# top_level.net
KiCad netlist of a schematic drawn in Altium Designer
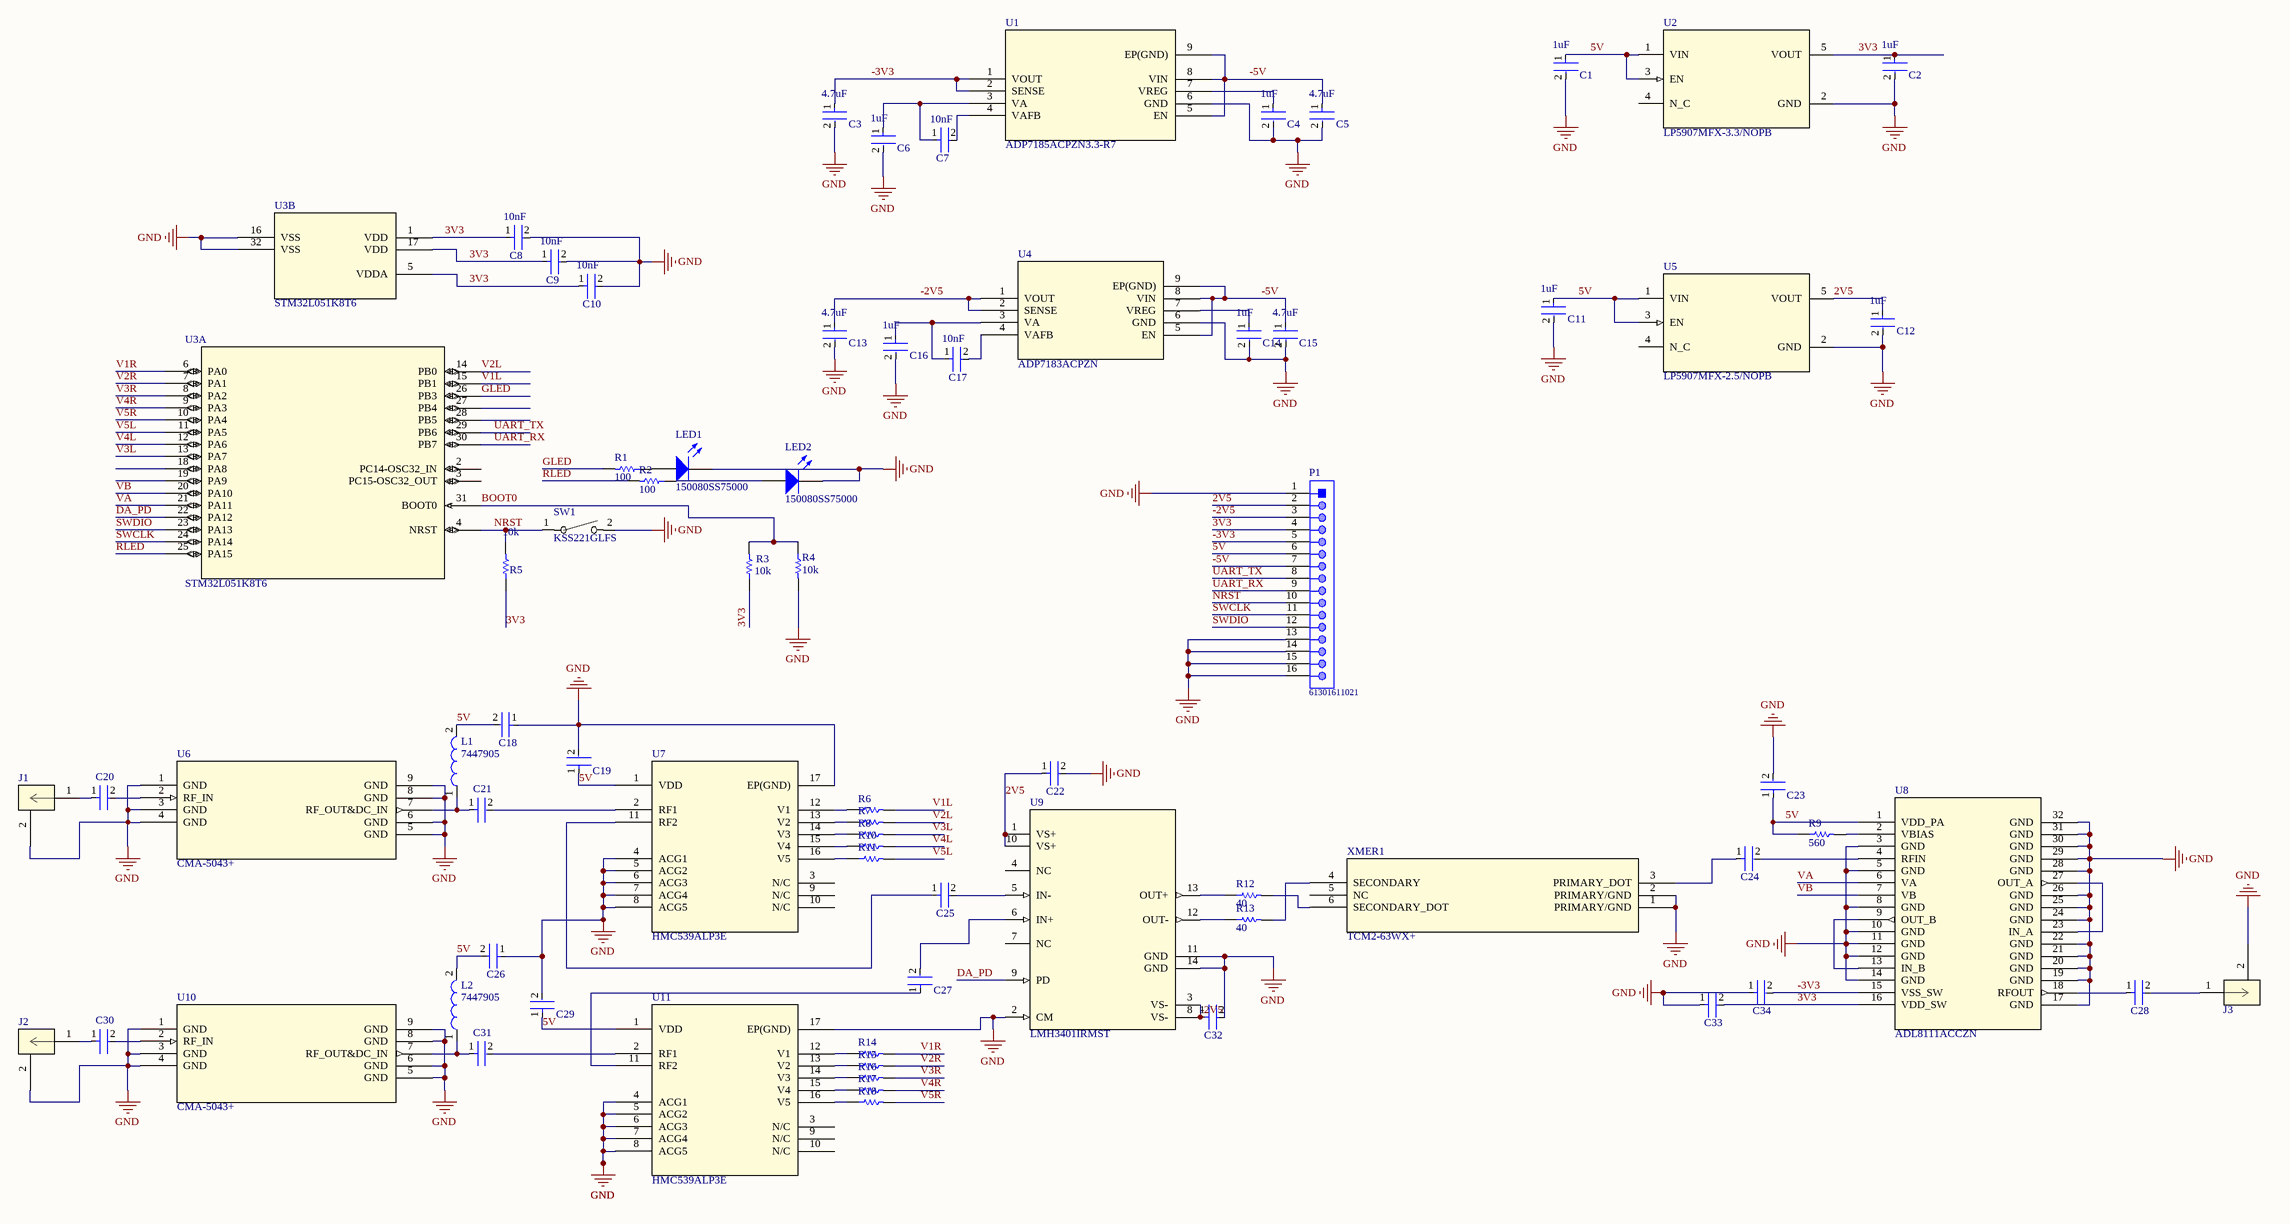
[diagram p0: top_level.SchDoc]

(export (version "E")
  (design (tool "Eeschema 10.0.6"))
  (components
    (comp (ref "C1")
      (value "1uF")
      (footprint "FP-C0402-BB-MFG")
      (description "CAP CER 0.1UF 10V X5R 0402")
      (fields (field (name "MANUFACTURER") "Kemet") (field (name "TOLERANCE") "0.1"))
      (libsource (lib "Altium Content Vault") (part "b4654b650e69147ec39a6b967a45e02"))
    )
    (comp (ref "C2")
      (value "1uF")
      (footprint "FP-C0402-BB-MFG")
      (description "CAP CER 0.1UF 10V X5R 0402")
      (fields (field (name "MANUFACTURER") "Kemet") (field (name "TOLERANCE") "0.1"))
      (libsource (lib "Altium Content Vault") (part "b4654b650e69147ec39a6b967a45e02"))
    )
    (comp (ref "C3")
      (value "4.7uF")
      (footprint "FP-C0402-BB-MFG")
      (description "CAP CER 0.1UF 10V X5R 0402")
      (fields (field (name "MANUFACTURER") "Kemet") (field (name "TOLERANCE") "0.1"))
      (libsource (lib "Altium Content Vault") (part "b4654b650e69147ec39a6b967a45e02"))
    )
    (comp (ref "C4")
      (value "1uF")
      (footprint "FP-C0402-BB-MFG")
      (description "CAP CER 0.1UF 10V X5R 0402")
      (fields (field (name "MANUFACTURER") "Kemet") (field (name "TOLERANCE") "0.1"))
      (libsource (lib "Altium Content Vault") (part "b4654b650e69147ec39a6b967a45e02"))
    )
    (comp (ref "C5")
      (value "4.7uF")
      (footprint "FP-C0402-BB-MFG")
      (description "CAP CER 0.1UF 10V X5R 0402")
      (fields (field (name "MANUFACTURER") "Kemet") (field (name "TOLERANCE") "0.1"))
      (libsource (lib "Altium Content Vault") (part "b4654b650e69147ec39a6b967a45e02"))
    )
    (comp (ref "C6")
      (value "1uF")
      (footprint "FP-C0402-BB-MFG")
      (description "CAP CER 0.1UF 10V X5R 0402")
      (fields (field (name "MANUFACTURER") "Kemet") (field (name "TOLERANCE") "0.1"))
      (libsource (lib "Altium Content Vault") (part "b4654b650e69147ec39a6b967a45e02"))
    )
    (comp (ref "C7")
      (value "10nF")
      (footprint "FP-C0402-BB-MFG")
      (description "CAP CER 0.1UF 10V X5R 0402")
      (fields (field (name "MANUFACTURER") "Kemet") (field (name "TOLERANCE") "0.1"))
      (libsource (lib "Altium Content Vault") (part "b4654b650e69147ec39a6b967a45e02"))
    )
    (comp (ref "C8")
      (value "10nF")
      (footprint "FP-C0402-BB-MFG")
      (description "CAP CER 0.1UF 10V X5R 0402")
      (fields (field (name "MANUFACTURER") "Kemet") (field (name "TOLERANCE") "0.1"))
      (libsource (lib "Altium Content Vault") (part "b4654b650e69147ec39a6b967a45e02"))
    )
    (comp (ref "C9")
      (value "10nF")
      (footprint "FP-C0402-BB-MFG")
      (description "CAP CER 0.1UF 10V X5R 0402")
      (fields (field (name "MANUFACTURER") "Kemet") (field (name "TOLERANCE") "0.1"))
      (libsource (lib "Altium Content Vault") (part "b4654b650e69147ec39a6b967a45e02"))
    )
    (comp (ref "C10")
      (value "10nF")
      (footprint "FP-C0402-BB-MFG")
      (description "CAP CER 0.1UF 10V X5R 0402")
      (fields (field (name "MANUFACTURER") "Kemet") (field (name "TOLERANCE") "0.1"))
      (libsource (lib "Altium Content Vault") (part "b4654b650e69147ec39a6b967a45e02"))
    )
    (comp (ref "C11")
      (value "1uF")
      (footprint "FP-C0402-BB-MFG")
      (description "CAP CER 0.1UF 10V X5R 0402")
      (fields (field (name "MANUFACTURER") "Kemet") (field (name "TOLERANCE") "0.1"))
      (libsource (lib "Altium Content Vault") (part "b4654b650e69147ec39a6b967a45e02"))
    )
    (comp (ref "C12")
      (value "1uF")
      (footprint "FP-C0402-BB-MFG")
      (description "CAP CER 0.1UF 10V X5R 0402")
      (fields (field (name "MANUFACTURER") "Kemet") (field (name "TOLERANCE") "0.1"))
      (libsource (lib "Altium Content Vault") (part "b4654b650e69147ec39a6b967a45e02"))
    )
    (comp (ref "C13")
      (value "4.7uF")
      (footprint "FP-C0402-BB-MFG")
      (description "CAP CER 0.1UF 10V X5R 0402")
      (fields (field (name "MANUFACTURER") "Kemet") (field (name "TOLERANCE") "0.1"))
      (libsource (lib "Altium Content Vault") (part "b4654b650e69147ec39a6b967a45e02"))
    )
    (comp (ref "C14")
      (value "1uF")
      (footprint "FP-C0402-BB-MFG")
      (description "CAP CER 0.1UF 10V X5R 0402")
      (fields (field (name "MANUFACTURER") "Kemet") (field (name "TOLERANCE") "0.1"))
      (libsource (lib "Altium Content Vault") (part "b4654b650e69147ec39a6b967a45e02"))
    )
    (comp (ref "C15")
      (value "4.7uF")
      (footprint "FP-C0402-BB-MFG")
      (description "CAP CER 0.1UF 10V X5R 0402")
      (fields (field (name "MANUFACTURER") "Kemet") (field (name "TOLERANCE") "0.1"))
      (libsource (lib "Altium Content Vault") (part "b4654b650e69147ec39a6b967a45e02"))
    )
    (comp (ref "C16")
      (value "1uF")
      (footprint "FP-C0402-BB-MFG")
      (description "CAP CER 0.1UF 10V X5R 0402")
      (fields (field (name "MANUFACTURER") "Kemet") (field (name "TOLERANCE") "0.1"))
      (libsource (lib "Altium Content Vault") (part "b4654b650e69147ec39a6b967a45e02"))
    )
    (comp (ref "C17")
      (value "10nF")
      (footprint "FP-C0402-BB-MFG")
      (description "CAP CER 0.1UF 10V X5R 0402")
      (fields (field (name "MANUFACTURER") "Kemet") (field (name "TOLERANCE") "0.1"))
      (libsource (lib "Altium Content Vault") (part "b4654b650e69147ec39a6b967a45e02"))
    )
    (comp (ref "C18")
      (value "C0402C104K8PACTU")
      (footprint "FP-C0402-BB-MFG")
      (description "CAP CER 0.1UF 10V X5R 0402")
      (fields (field (name "MANUFACTURER") "Kemet") (field (name "TOLERANCE") "0.1"))
      (libsource (lib "Altium Content Vault") (part "b4654b650e69147ec39a6b967a45e02"))
    )
    (comp (ref "C19")
      (value "C0402C104K8PACTU")
      (footprint "FP-C0402-BB-MFG")
      (description "CAP CER 0.1UF 10V X5R 0402")
      (fields (field (name "MANUFACTURER") "Kemet") (field (name "TOLERANCE") "0.1"))
      (libsource (lib "Altium Content Vault") (part "b4654b650e69147ec39a6b967a45e02"))
    )
    (comp (ref "C20")
      (value "C0402C104K8PACTU")
      (footprint "FP-C0402-BB-MFG")
      (description "CAP CER 0.1UF 10V X5R 0402")
      (fields (field (name "MANUFACTURER") "Kemet") (field (name "TOLERANCE") "0.1"))
      (libsource (lib "Altium Content Vault") (part "b4654b650e69147ec39a6b967a45e02"))
    )
    (comp (ref "C21")
      (value "C0402C104K8PACTU")
      (footprint "FP-C0402-BB-MFG")
      (description "CAP CER 0.1UF 10V X5R 0402")
      (fields (field (name "MANUFACTURER") "Kemet") (field (name "TOLERANCE") "0.1"))
      (libsource (lib "Altium Content Vault") (part "b4654b650e69147ec39a6b967a45e02"))
    )
    (comp (ref "C22")
      (value "C0402C104K8PACTU")
      (footprint "FP-C0402-BB-MFG")
      (description "CAP CER 0.1UF 10V X5R 0402")
      (fields (field (name "MANUFACTURER") "Kemet") (field (name "TOLERANCE") "0.1"))
      (libsource (lib "Altium Content Vault") (part "b4654b650e69147ec39a6b967a45e02"))
    )
    (comp (ref "C23")
      (value "C0402C104K8PACTU")
      (footprint "FP-C0402-BB-MFG")
      (description "CAP CER 0.1UF 10V X5R 0402")
      (fields (field (name "MANUFACTURER") "Kemet") (field (name "TOLERANCE") "0.1"))
      (libsource (lib "Altium Content Vault") (part "b4654b650e69147ec39a6b967a45e02"))
    )
    (comp (ref "C24")
      (value "C0402C104K8PACTU")
      (footprint "FP-C0402-BB-MFG")
      (description "CAP CER 0.1UF 10V X5R 0402")
      (fields (field (name "MANUFACTURER") "Kemet") (field (name "TOLERANCE") "0.1"))
      (libsource (lib "Altium Content Vault") (part "b4654b650e69147ec39a6b967a45e02"))
    )
    (comp (ref "C25")
      (value "C0402C104K8PACTU")
      (footprint "FP-C0402-BB-MFG")
      (description "CAP CER 0.1UF 10V X5R 0402")
      (fields (field (name "MANUFACTURER") "Kemet") (field (name "TOLERANCE") "0.1"))
      (libsource (lib "Altium Content Vault") (part "b4654b650e69147ec39a6b967a45e02"))
    )
    (comp (ref "C26")
      (value "C0402C104K8PACTU")
      (footprint "FP-C0402-BB-MFG")
      (description "CAP CER 0.1UF 10V X5R 0402")
      (fields (field (name "MANUFACTURER") "Kemet") (field (name "TOLERANCE") "0.1"))
      (libsource (lib "Altium Content Vault") (part "b4654b650e69147ec39a6b967a45e02"))
    )
    (comp (ref "C27")
      (value "C0402C104K8PACTU")
      (footprint "FP-C0402-BB-MFG")
      (description "CAP CER 0.1UF 10V X5R 0402")
      (fields (field (name "MANUFACTURER") "Kemet") (field (name "TOLERANCE") "0.1"))
      (libsource (lib "Altium Content Vault") (part "b4654b650e69147ec39a6b967a45e02"))
    )
    (comp (ref "C28")
      (value "C0402C104K8PACTU")
      (footprint "FP-C0402-BB-MFG")
      (description "CAP CER 0.1UF 10V X5R 0402")
      (fields (field (name "MANUFACTURER") "Kemet") (field (name "TOLERANCE") "0.1"))
      (libsource (lib "Altium Content Vault") (part "b4654b650e69147ec39a6b967a45e02"))
    )
    (comp (ref "C29")
      (value "C0402C104K8PACTU")
      (footprint "FP-C0402-BB-MFG")
      (description "CAP CER 0.1UF 10V X5R 0402")
      (fields (field (name "MANUFACTURER") "Kemet") (field (name "TOLERANCE") "0.1"))
      (libsource (lib "Altium Content Vault") (part "b4654b650e69147ec39a6b967a45e02"))
    )
    (comp (ref "C30")
      (value "C0402C104K8PACTU")
      (footprint "FP-C0402-BB-MFG")
      (description "CAP CER 0.1UF 10V X5R 0402")
      (fields (field (name "MANUFACTURER") "Kemet") (field (name "TOLERANCE") "0.1"))
      (libsource (lib "Altium Content Vault") (part "b4654b650e69147ec39a6b967a45e02"))
    )
    (comp (ref "C31")
      (value "C0402C104K8PACTU")
      (footprint "FP-C0402-BB-MFG")
      (description "CAP CER 0.1UF 10V X5R 0402")
      (fields (field (name "MANUFACTURER") "Kemet") (field (name "TOLERANCE") "0.1"))
      (libsource (lib "Altium Content Vault") (part "b4654b650e69147ec39a6b967a45e02"))
    )
    (comp (ref "C32")
      (value "C0402C104K8PACTU")
      (footprint "FP-C0402-BB-MFG")
      (description "CAP CER 0.1UF 10V X5R 0402")
      (fields (field (name "MANUFACTURER") "Kemet") (field (name "TOLERANCE") "0.1"))
      (libsource (lib "Altium Content Vault") (part "b4654b650e69147ec39a6b967a45e02"))
    )
    (comp (ref "C33")
      (value "C0402C104K8PACTU")
      (footprint "FP-C0402-BB-MFG")
      (description "CAP CER 0.1UF 10V X5R 0402")
      (fields (field (name "MANUFACTURER") "Kemet") (field (name "TOLERANCE") "0.1"))
      (libsource (lib "Altium Content Vault") (part "b4654b650e69147ec39a6b967a45e02"))
    )
    (comp (ref "C34")
      (value "C0402C104K8PACTU")
      (footprint "FP-C0402-BB-MFG")
      (description "CAP CER 0.1UF 10V X5R 0402")
      (fields (field (name "MANUFACTURER") "Kemet") (field (name "TOLERANCE") "0.1"))
      (libsource (lib "Altium Content Vault") (part "b4654b650e69147ec39a6b967a45e02"))
    )
    (comp (ref "J1")
      (value "142-0711-821")
      (footprint "CONN_142-0711-821_CIN")
      (description "No Description Available")
      (fields (field (name "COPYRIGHT") "Copyright (C) 2022 Ultra Librarian. All rights reserved."))
      (libsource (lib "") (part "142-0711-821_1"))
    )
    (comp (ref "J2")
      (value "142-0711-821")
      (footprint "CONN_142-0711-821_CIN")
      (description "No Description Available")
      (fields (field (name "COPYRIGHT") "Copyright (C) 2022 Ultra Librarian. All rights reserved."))
      (libsource (lib "") (part "142-0711-821_1"))
    )
    (comp (ref "J3")
      (value "142-0711-821")
      (footprint "CONN_142-0711-821_CIN")
      (description "No Description Available")
      (fields (field (name "COPYRIGHT") "Copyright (C) 2022 Ultra Librarian. All rights reserved."))
      (libsource (lib "142-0711-821") (part "142-0711-821"))
    )
    (comp (ref "L1")
      (value "7447905")
      (footprint "SMD-0805")
      (description "SMD-Multilayer Inductor WE-MI, L = 1.00 µH")
      (libsource (lib "Altium Content Vault") (part "PAS-IND-INDUCTOR-2"))
    )
    (comp (ref "L2")
      (value "7447905")
      (footprint "SMD-0805")
      (description "SMD-Multilayer Inductor WE-MI, L = 1.00 µH")
      (libsource (lib "Altium Content Vault") (part "PAS-IND-INDUCTOR-2"))
    )
    (comp (ref "LED1")
      (value "150080SS75000")
      (footprint "0805_A")
      (description "SMD mono-color Chip LED, WL-SMCW, Super Red")
      (fields (field (name "MANUFACTURER") "Wuerth Elektronik"))
      (libsource (lib "Altium Content Vault") (part "WE-LED_K1A2-2"))
    )
    (comp (ref "LED2")
      (value "150080SS75000")
      (footprint "0805_A")
      (description "SMD mono-color Chip LED, WL-SMCW, Super Red")
      (fields (field (name "MANUFACTURER") "Wuerth Elektronik"))
      (libsource (lib "Altium Content Vault") (part "WE-LED_K1A2-2"))
    )
    (comp (ref "P1")
      (value "61301611021")
      (footprint "61301611021")
      (description "THT Angled Pin Header WR-PHD, Pitch 2.54 mm, Single Row, 16 pins")
      (fields (field (name "MANUFACTURER") "Wurth Elektronik") (field (name "PUBLISHER") "WurthElektronik"))
      (libsource (lib "Altium Content Vault") (part "WE-CN-1P-M-R16"))
    )
    (comp (ref "R1")
      (value "100")
      (footprint "RESC1005X40X25NL05T10")
      (fields (field (name "MANUFACTURER") "Yageo / Phycomp") (field (name "PART NUMBER") "RC0402JR-070RL"))
      (libsource (lib "Altium Content Vault") (part "RES"))
    )
    (comp (ref "R2")
      (value "100")
      (footprint "RESC1005X40X25NL05T10")
      (fields (field (name "MANUFACTURER") "Yageo / Phycomp") (field (name "PART NUMBER") "RC0402JR-070RL"))
      (libsource (lib "Altium Content Vault") (part "RES"))
    )
    (comp (ref "R3")
      (value "10k")
      (footprint "RESC1005X40X25NL05T10")
      (fields (field (name "MANUFACTURER") "Yageo / Phycomp") (field (name "PART NUMBER") "RC0402JR-070RL"))
      (libsource (lib "Altium Content Vault") (part "RES"))
    )
    (comp (ref "R4")
      (value "10k")
      (footprint "RESC1005X40X25NL05T10")
      (fields (field (name "MANUFACTURER") "Yageo / Phycomp") (field (name "PART NUMBER") "RC0402JR-070RL"))
      (libsource (lib "Altium Content Vault") (part "RES"))
    )
    (comp (ref "R5")
      (value "10k")
      (footprint "RESC1005X40X25NL05T10")
      (fields (field (name "MANUFACTURER") "Yageo / Phycomp") (field (name "PART NUMBER") "RC0402JR-070RL"))
      (libsource (lib "Altium Content Vault") (part "RES"))
    )
    (comp (ref "R6")
      (value "RC0402JR-070RL")
      (footprint "RESC1005X40X25NL05T10")
      (fields (field (name "MANUFACTURER") "Yageo / Phycomp"))
      (libsource (lib "Altium Content Vault") (part "RES"))
    )
    (comp (ref "R7")
      (value "RC0402JR-070RL")
      (footprint "RESC1005X40X25NL05T10")
      (fields (field (name "MANUFACTURER") "Yageo / Phycomp"))
      (libsource (lib "Altium Content Vault") (part "RES"))
    )
    (comp (ref "R8")
      (value "RC0402JR-070RL")
      (footprint "RESC1005X40X25NL05T10")
      (fields (field (name "MANUFACTURER") "Yageo / Phycomp"))
      (libsource (lib "Altium Content Vault") (part "RES"))
    )
    (comp (ref "R9")
      (value "560")
      (footprint "RESC1005X40X25NL05T10")
      (fields (field (name "MANUFACTURER") "Yageo / Phycomp") (field (name "PART NUMBER") "RC0402JR-070RL"))
      (libsource (lib "Altium Content Vault") (part "RES"))
    )
    (comp (ref "R10")
      (value "RC0402JR-070RL")
      (footprint "RESC1005X40X25NL05T10")
      (fields (field (name "MANUFACTURER") "Yageo / Phycomp"))
      (libsource (lib "Altium Content Vault") (part "RES"))
    )
    (comp (ref "R11")
      (value "RC0402JR-070RL")
      (footprint "RESC1005X40X25NL05T10")
      (fields (field (name "MANUFACTURER") "Yageo / Phycomp"))
      (libsource (lib "Altium Content Vault") (part "RES"))
    )
    (comp (ref "R12")
      (value "40")
      (footprint "RESC1005X40X25NL05T10")
      (fields (field (name "MANUFACTURER") "Yageo / Phycomp") (field (name "PART NUMBER") "RC0402JR-070RL"))
      (libsource (lib "Altium Content Vault") (part "RES"))
    )
    (comp (ref "R13")
      (value "40")
      (footprint "RESC1005X40X25NL05T10")
      (fields (field (name "MANUFACTURER") "Yageo / Phycomp") (field (name "PART NUMBER") "RC0402JR-070RL"))
      (libsource (lib "Altium Content Vault") (part "RES"))
    )
    (comp (ref "R14")
      (value "RC0402JR-070RL")
      (footprint "RESC1005X40X25NL05T10")
      (fields (field (name "MANUFACTURER") "Yageo / Phycomp"))
      (libsource (lib "Altium Content Vault") (part "RES"))
    )
    (comp (ref "R15")
      (value "RC0402JR-070RL")
      (footprint "RESC1005X40X25NL05T10")
      (fields (field (name "MANUFACTURER") "Yageo / Phycomp"))
      (libsource (lib "Altium Content Vault") (part "RES"))
    )
    (comp (ref "R16")
      (value "RC0402JR-070RL")
      (footprint "RESC1005X40X25NL05T10")
      (fields (field (name "MANUFACTURER") "Yageo / Phycomp"))
      (libsource (lib "Altium Content Vault") (part "RES"))
    )
    (comp (ref "R17")
      (value "RC0402JR-070RL")
      (footprint "RESC1005X40X25NL05T10")
      (fields (field (name "MANUFACTURER") "Yageo / Phycomp"))
      (libsource (lib "Altium Content Vault") (part "RES"))
    )
    (comp (ref "R18")
      (value "RC0402JR-070RL")
      (footprint "RESC1005X40X25NL05T10")
      (fields (field (name "MANUFACTURER") "Yageo / Phycomp"))
      (libsource (lib "Altium Content Vault") (part "RES"))
    )
    (comp (ref "SW1")
      (value "KSS221GLFS")
      (footprint "SW_KSS221GLFS_CNK")
      (description "No Description Available")
      (fields (field (name "COPYRIGHT") "Copyright (C) 2022 Ultra Librarian. All rights reserved."))
      (libsource (lib "KSS221GLFS") (part "KSS221GLFS"))
    )
    (comp (ref "U1")
      (value "ADP7185ACPZN3.3-R7")
      (footprint "CP_8_27_ADI")
      (description "No Description Available")
      (fields (field (name "COPYRIGHT") "Copyright (C) 2022 Ultra Librarian. All rights reserved."))
      (libsource (lib "ADP7185ACPZN3P3-R7") (part "ADP7185ACPZN3.3-R7"))
    )
    (comp (ref "U2")
      (value "LP5907MFX-3.3/NOPB")
      (footprint "DBV0005A_L")
      (description "No Description Available")
      (fields (field (name "COPYRIGHT") "Copyright (C) 2022 Ultra Librarian. All rights reserved."))
      (libsource (lib "LP5907MFX-3P3&slash_NOPB") (part "LP5907MFX-3.3/NOPB"))
    )
    (comp (ref "U3")
      (value "STM32L051K8T6")
      (footprint "LQFP32_7X7X1P4")
      (description "No Description Available")
      (fields (field (name "COPYRIGHT") "Copyright (C) 2022 Ultra Librarian. All rights reserved."))
      (libsource (lib "STM32L051K8T6") (part "STM32L051K8T6"))
    )
    (comp (ref "U4")
      (value "ADP7183ACPZN")
      (footprint "CP-8-27_ADI")
      (description "No Description Available")
      (fields (field (name "COPYRIGHT") "Copyright (C) 2022 Ultra Librarian. All rights reserved."))
      (libsource (lib "ADP7183ACPZN") (part "ADP7183ACPZN"))
    )
    (comp (ref "U5")
      (value "LP5907MFX-2.5/NOPB")
      (footprint "DBV0005A_L")
      (description "No Description Available")
      (fields (field (name "COPYRIGHT") "Copyright (C) 2022 Ultra Librarian. All rights reserved."))
      (libsource (lib "LP5907MFX-2P5&slash_NOPB") (part "LP5907MFX-2.5/NOPB"))
    )
    (comp (ref "U6")
      (value "CMA-5043+")
      (footprint "DL1721_MNC")
      (description "No Description Available")
      (fields (field (name "COPYRIGHT") "Copyright (C) 2022 Ultra Librarian. All rights reserved."))
      (libsource (lib "CMA-5043&plus_") (part "CMA-5043+"))
    )
    (comp (ref "U7")
      (value "HMC539ALP3E")
      (footprint "HCP_16_1_ADI")
      (description "No Description Available")
      (fields (field (name "COPYRIGHT") "Copyright (C) 2022 Ultra Librarian. All rights reserved."))
      (libsource (lib "HMC539ALP3E") (part "HMC539ALP3E"))
    )
    (comp (ref "U8")
      (value "ADL8111ACCZN")
      (footprint "IC28_ADL8111ACCZN_ADI")
      (description "No Description Available")
      (fields (field (name "COPYRIGHT") "Copyright (C) 2022 Ultra Librarian. All rights reserved."))
      (libsource (lib "ADL8111ACCZN") (part "ADL8111ACCZN"))
    )
    (comp (ref "U9")
      (value "LMH3401IRMST")
      (footprint "RMS0014A")
      (description "No Description Available")
      (fields (field (name "COPYRIGHT") "Copyright (C) 2022 Ultra Librarian. All rights reserved."))
      (libsource (lib "LMH3401IRMST") (part "LMH3401IRMST"))
    )
    (comp (ref "U10")
      (value "CMA-5043+")
      (footprint "DL1721_MNC")
      (description "No Description Available")
      (fields (field (name "COPYRIGHT") "Copyright (C) 2022 Ultra Librarian. All rights reserved."))
      (libsource (lib "CMA-5043&plus_") (part "CMA-5043+"))
    )
    (comp (ref "U11")
      (value "HMC539ALP3E")
      (footprint "HCP_16_1_ADI")
      (description "No Description Available")
      (fields (field (name "COPYRIGHT") "Copyright (C) 2022 Ultra Librarian. All rights reserved."))
      (libsource (lib "HMC539ALP3E") (part "HMC539ALP3E"))
    )
    (comp (ref "XMER1")
      (value "TCM2-63WX+")
      (footprint "DB1627_MNC")
      (description "No Description Available")
      (fields (field (name "COPYRIGHT") "Copyright (C) 2022 Ultra Librarian. All rights reserved."))
      (libsource (lib "TCM2-63WX&plus_") (part "TCM2-63WX+"))
    )
  )
  (nets
    (net (code "1") (name "/-2V5") (class "Default")
      (node (ref "C13") (pin "1") (pinfunction "1_1") (pintype "passive"))
      (node (ref "C32") (pin "1") (pinfunction "1_1") (pintype "passive"))
      (node (ref "P1") (pin "3") (pinfunction "3_3") (pintype "passive"))
      (node (ref "U4") (pin "1") (pinfunction "VOUT_1") (pintype "passive"))
      (node (ref "U4") (pin "2") (pinfunction "SENSE_2") (pintype "passive"))
      (node (ref "U9") (pin "3") (pinfunction "VS-_3") (pintype "power_in"))
      (node (ref "U9") (pin "8") (pinfunction "VS-_8") (pintype "power_in"))
    )
    (net (code "2") (name "/-3V3") (class "Default")
      (node (ref "C3") (pin "1") (pinfunction "1_1") (pintype "passive"))
      (node (ref "C34") (pin "2") (pinfunction "2_2") (pintype "passive"))
      (node (ref "P1") (pin "5") (pinfunction "5_5") (pintype "passive"))
      (node (ref "U1") (pin "1") (pinfunction "VOUT_1") (pintype "passive"))
      (node (ref "U1") (pin "2") (pinfunction "SENSE_2") (pintype "passive"))
      (node (ref "U8") (pin "15") (pinfunction "VSS_SW_15") (pintype "passive"))
    )
    (net (code "3") (name "/-5V") (class "Default")
      (node (ref "C15") (pin "1") (pinfunction "1_1") (pintype "passive"))
      (node (ref "C5") (pin "1") (pinfunction "1_1") (pintype "passive"))
      (node (ref "P1") (pin "7") (pinfunction "7_7") (pintype "passive"))
      (node (ref "U1") (pin "5") (pinfunction "EN_5") (pintype "passive"))
      (node (ref "U1") (pin "8") (pinfunction "VIN_8") (pintype "passive"))
      (node (ref "U1") (pin "9") (pinfunction "EP(GND)_9") (pintype "passive"))
      (node (ref "U4") (pin "5") (pinfunction "EN_5") (pintype "passive"))
      (node (ref "U4") (pin "8") (pinfunction "VIN_8") (pintype "passive"))
      (node (ref "U4") (pin "9") (pinfunction "EP(GND)_9") (pintype "passive"))
    )
    (net (code "4") (name "/2V5") (class "Default")
      (node (ref "C12") (pin "1") (pinfunction "1_1") (pintype "passive"))
      (node (ref "C22") (pin "1") (pinfunction "1_1") (pintype "passive"))
      (node (ref "P1") (pin "2") (pinfunction "2_2") (pintype "passive"))
      (node (ref "U5") (pin "5") (pinfunction "VOUT_5") (pintype "power_in"))
      (node (ref "U9") (pin "1") (pinfunction "VS+_1") (pintype "power_in"))
      (node (ref "U9") (pin "10") (pinfunction "VS+_10") (pintype "power_in"))
    )
    (net (code "5") (name "/3V3") (class "Default")
      (node (ref "C10") (pin "1") (pinfunction "1_1") (pintype "passive"))
      (node (ref "C2") (pin "1") (pinfunction "1_1") (pintype "passive"))
      (node (ref "C33") (pin "2") (pinfunction "2_2") (pintype "passive"))
      (node (ref "C8") (pin "1") (pinfunction "1_1") (pintype "passive"))
      (node (ref "C9") (pin "1") (pinfunction "1_1") (pintype "passive"))
      (node (ref "P1") (pin "4") (pinfunction "4_4") (pintype "passive"))
      (node (ref "R3") (pin "1") (pinfunction "1_1") (pintype "passive"))
      (node (ref "R5") (pin "1") (pinfunction "1_1") (pintype "passive"))
      (node (ref "U2") (pin "5") (pinfunction "VOUT_5") (pintype "power_in"))
      (node (ref "U3") (pin "1") (pinfunction "VDD_1") (pintype "power_in"))
      (node (ref "U3") (pin "17") (pinfunction "VDD_17") (pintype "power_in"))
      (node (ref "U3") (pin "5") (pinfunction "VDDA_5") (pintype "power_in"))
      (node (ref "U8") (pin "16") (pinfunction "VDD_SW_16") (pintype "power_in"))
    )
    (net (code "6") (name "/5V") (class "Default")
      (node (ref "C1") (pin "1") (pinfunction "1_1") (pintype "passive"))
      (node (ref "C11") (pin "1") (pinfunction "1_1") (pintype "passive"))
      (node (ref "C18") (pin "2") (pinfunction "2_2") (pintype "passive"))
      (node (ref "C19") (pin "1") (pinfunction "1_1") (pintype "passive"))
      (node (ref "C23") (pin "1") (pinfunction "1_1") (pintype "passive"))
      (node (ref "C26") (pin "2") (pinfunction "2_2") (pintype "passive"))
      (node (ref "C29") (pin "1") (pinfunction "1_1") (pintype "passive"))
      (node (ref "L1") (pin "2") (pinfunction "2_2") (pintype "passive"))
      (node (ref "L2") (pin "2") (pinfunction "2_2") (pintype "passive"))
      (node (ref "P1") (pin "6") (pinfunction "6_6") (pintype "passive"))
      (node (ref "R9") (pin "1") (pinfunction "1_1") (pintype "passive"))
      (node (ref "U11") (pin "1") (pinfunction "VDD_1") (pintype "passive"))
      (node (ref "U2") (pin "1") (pinfunction "VIN_1") (pintype "power_in"))
      (node (ref "U2") (pin "3") (pinfunction "EN_3") (pintype "input"))
      (node (ref "U5") (pin "1") (pinfunction "VIN_1") (pintype "power_in"))
      (node (ref "U5") (pin "3") (pinfunction "EN_3") (pintype "input"))
      (node (ref "U7") (pin "1") (pinfunction "VDD_1") (pintype "passive"))
      (node (ref "U8") (pin "1") (pinfunction "VDD_PA_1") (pintype "power_in"))
    )
    (net (code "7") (name "/BOOT0") (class "Default")
      (node (ref "R3") (pin "2") (pinfunction "2_2") (pintype "passive"))
      (node (ref "R4") (pin "1") (pinfunction "1_1") (pintype "passive"))
      (node (ref "U3") (pin "31") (pinfunction "BOOT0_31") (pintype "input"))
    )
    (net (code "8") (name "/DA_PD") (class "Default")
      (node (ref "U3") (pin "22") (pinfunction "PA12_22") (pintype "bidirectional"))
      (node (ref "U9") (pin "9") (pinfunction "PD_9") (pintype "input"))
    )
    (net (code "9") (name "/GLED") (class "Default")
      (node (ref "R1") (pin "2") (pinfunction "2_2") (pintype "passive"))
      (node (ref "U3") (pin "26") (pinfunction "PB3_26") (pintype "bidirectional"))
    )
    (net (code "10") (name "/NRST") (class "Default")
      (node (ref "P1") (pin "10") (pinfunction "10_10") (pintype "passive"))
      (node (ref "R5") (pin "2") (pinfunction "2_2") (pintype "passive"))
      (node (ref "SW1") (pin "1") (pinfunction "1_1") (pintype "passive"))
      (node (ref "U3") (pin "4") (pinfunction "NRST_4") (pintype "bidirectional"))
    )
    (net (code "11") (name "/RLED") (class "Default")
      (node (ref "R2") (pin "2") (pinfunction "2_2") (pintype "passive"))
      (node (ref "U3") (pin "25") (pinfunction "PA15_25") (pintype "bidirectional"))
    )
    (net (code "12") (name "/SWCLK") (class "Default")
      (node (ref "P1") (pin "11") (pinfunction "11_11") (pintype "passive"))
      (node (ref "U3") (pin "24") (pinfunction "PA14_24") (pintype "bidirectional"))
    )
    (net (code "13") (name "/SWDIO") (class "Default")
      (node (ref "P1") (pin "12") (pinfunction "12_12") (pintype "passive"))
      (node (ref "U3") (pin "23") (pinfunction "PA13_23") (pintype "bidirectional"))
    )
    (net (code "14") (name "/UART_RX") (class "Default")
      (node (ref "P1") (pin "9") (pinfunction "9_9") (pintype "passive"))
      (node (ref "U3") (pin "30") (pinfunction "PB7_30") (pintype "bidirectional"))
    )
    (net (code "15") (name "/UART_TX") (class "Default")
      (node (ref "P1") (pin "8") (pinfunction "8_8") (pintype "passive"))
      (node (ref "U3") (pin "29") (pinfunction "PB6_29") (pintype "bidirectional"))
    )
    (net (code "16") (name "/V1L") (class "Default")
      (node (ref "R6") (pin "2") (pinfunction "2_2") (pintype "passive"))
      (node (ref "U3") (pin "15") (pinfunction "PB1_15") (pintype "bidirectional"))
    )
    (net (code "17") (name "/V1R") (class "Default")
      (node (ref "R14") (pin "2") (pinfunction "2_2") (pintype "passive"))
      (node (ref "U3") (pin "6") (pinfunction "PA0_6") (pintype "bidirectional"))
    )
    (net (code "18") (name "/V2L") (class "Default")
      (node (ref "R7") (pin "2") (pinfunction "2_2") (pintype "passive"))
      (node (ref "U3") (pin "14") (pinfunction "PB0_14") (pintype "bidirectional"))
    )
    (net (code "19") (name "/V2R") (class "Default")
      (node (ref "R15") (pin "2") (pinfunction "2_2") (pintype "passive"))
      (node (ref "U3") (pin "7") (pinfunction "PA1_7") (pintype "bidirectional"))
    )
    (net (code "20") (name "/V3L") (class "Default")
      (node (ref "R8") (pin "2") (pinfunction "2_2") (pintype "passive"))
      (node (ref "U3") (pin "13") (pinfunction "PA7_13") (pintype "bidirectional"))
    )
    (net (code "21") (name "/V3R") (class "Default")
      (node (ref "R16") (pin "2") (pinfunction "2_2") (pintype "passive"))
      (node (ref "U3") (pin "8") (pinfunction "PA2_8") (pintype "bidirectional"))
    )
    (net (code "22") (name "/V4L") (class "Default")
      (node (ref "R10") (pin "2") (pinfunction "2_2") (pintype "passive"))
      (node (ref "U3") (pin "12") (pinfunction "PA6_12") (pintype "bidirectional"))
    )
    (net (code "23") (name "/V4R") (class "Default")
      (node (ref "R17") (pin "2") (pinfunction "2_2") (pintype "passive"))
      (node (ref "U3") (pin "9") (pinfunction "PA3_9") (pintype "bidirectional"))
    )
    (net (code "24") (name "/V5L") (class "Default")
      (node (ref "R11") (pin "2") (pinfunction "2_2") (pintype "passive"))
      (node (ref "U3") (pin "11") (pinfunction "PA5_11") (pintype "bidirectional"))
    )
    (net (code "25") (name "/V5R") (class "Default")
      (node (ref "R18") (pin "2") (pinfunction "2_2") (pintype "passive"))
      (node (ref "U3") (pin "10") (pinfunction "PA4_10") (pintype "bidirectional"))
    )
    (net (code "26") (name "/VA") (class "Default")
      (node (ref "U3") (pin "21") (pinfunction "PA11_21") (pintype "bidirectional"))
      (node (ref "U8") (pin "6") (pinfunction "VA_6") (pintype "passive"))
    )
    (net (code "27") (name "/VB") (class "Default")
      (node (ref "U3") (pin "20") (pinfunction "PA10_20") (pintype "bidirectional"))
      (node (ref "U8") (pin "7") (pinfunction "VB_7") (pintype "passive"))
    )
    (net (code "28") (name "GND") (class "Default")
      (node (ref "C1") (pin "2") (pinfunction "2_2") (pintype "passive"))
      (node (ref "C10") (pin "2") (pinfunction "2_2") (pintype "passive"))
      (node (ref "C11") (pin "2") (pinfunction "2_2") (pintype "passive"))
      (node (ref "C12") (pin "2") (pinfunction "2_2") (pintype "passive"))
      (node (ref "C13") (pin "2") (pinfunction "2_2") (pintype "passive"))
      (node (ref "C14") (pin "2") (pinfunction "2_2") (pintype "passive"))
      (node (ref "C15") (pin "2") (pinfunction "2_2") (pintype "passive"))
      (node (ref "C16") (pin "2") (pinfunction "2_2") (pintype "passive"))
      (node (ref "C18") (pin "1") (pinfunction "1_1") (pintype "passive"))
      (node (ref "C19") (pin "2") (pinfunction "2_2") (pintype "passive"))
      (node (ref "C2") (pin "2") (pinfunction "2_2") (pintype "passive"))
      (node (ref "C22") (pin "2") (pinfunction "2_2") (pintype "passive"))
      (node (ref "C23") (pin "2") (pinfunction "2_2") (pintype "passive"))
      (node (ref "C26") (pin "1") (pinfunction "1_1") (pintype "passive"))
      (node (ref "C29") (pin "2") (pinfunction "2_2") (pintype "passive"))
      (node (ref "C3") (pin "2") (pinfunction "2_2") (pintype "passive"))
      (node (ref "C32") (pin "2") (pinfunction "2_2") (pintype "passive"))
      (node (ref "C33") (pin "1") (pinfunction "1_1") (pintype "passive"))
      (node (ref "C34") (pin "1") (pinfunction "1_1") (pintype "passive"))
      (node (ref "C4") (pin "2") (pinfunction "2_2") (pintype "passive"))
      (node (ref "C5") (pin "2") (pinfunction "2_2") (pintype "passive"))
      (node (ref "C6") (pin "2") (pinfunction "2_2") (pintype "passive"))
      (node (ref "C8") (pin "2") (pinfunction "2_2") (pintype "passive"))
      (node (ref "C9") (pin "2") (pinfunction "2_2") (pintype "passive"))
      (node (ref "J1") (pin "2") (pintype "passive"))
      (node (ref "J2") (pin "2") (pintype "passive"))
      (node (ref "J3") (pin "2") (pintype "passive"))
      (node (ref "LED1") (pin "1") (pinfunction "K_1") (pintype "passive"))
      (node (ref "LED2") (pin "1") (pinfunction "K_1") (pintype "passive"))
      (node (ref "P1") (pin "1") (pinfunction "1_1") (pintype "passive"))
      (node (ref "P1") (pin "13") (pinfunction "13_13") (pintype "passive"))
      (node (ref "P1") (pin "14") (pinfunction "14_14") (pintype "passive"))
      (node (ref "P1") (pin "15") (pinfunction "15_15") (pintype "passive"))
      (node (ref "P1") (pin "16") (pinfunction "16_16") (pintype "passive"))
      (node (ref "R4") (pin "2") (pinfunction "2_2") (pintype "passive"))
      (node (ref "SW1") (pin "2") (pinfunction "2_2") (pintype "passive"))
      (node (ref "U1") (pin "6") (pinfunction "GND_6") (pintype "passive"))
      (node (ref "U10") (pin "1") (pinfunction "GND_1") (pintype "passive"))
      (node (ref "U10") (pin "3") (pinfunction "GND_3") (pintype "passive"))
      (node (ref "U10") (pin "4") (pinfunction "GND_4") (pintype "passive"))
      (node (ref "U10") (pin "5") (pinfunction "GND_5") (pintype "passive"))
      (node (ref "U10") (pin "6") (pinfunction "GND_6") (pintype "passive"))
      (node (ref "U10") (pin "8") (pinfunction "GND_8") (pintype "passive"))
      (node (ref "U10") (pin "9") (pinfunction "GND_9") (pintype "passive"))
      (node (ref "U11") (pin "17") (pinfunction "EP(GND)_17") (pintype "passive"))
      (node (ref "U11") (pin "4") (pinfunction "ACG1_4") (pintype "passive"))
      (node (ref "U11") (pin "5") (pinfunction "ACG2_5") (pintype "passive"))
      (node (ref "U11") (pin "6") (pinfunction "ACG3_6") (pintype "passive"))
      (node (ref "U11") (pin "7") (pinfunction "ACG4_7") (pintype "passive"))
      (node (ref "U11") (pin "8") (pinfunction "ACG5_8") (pintype "passive"))
      (node (ref "U2") (pin "2") (pinfunction "GND_2") (pintype "power_in"))
      (node (ref "U3") (pin "16") (pinfunction "VSS_16") (pintype "power_in"))
      (node (ref "U3") (pin "32") (pinfunction "VSS_32") (pintype "power_in"))
      (node (ref "U4") (pin "6") (pinfunction "GND_6") (pintype "passive"))
      (node (ref "U5") (pin "2") (pinfunction "GND_2") (pintype "power_in"))
      (node (ref "U6") (pin "1") (pinfunction "GND_1") (pintype "passive"))
      (node (ref "U6") (pin "3") (pinfunction "GND_3") (pintype "passive"))
      (node (ref "U6") (pin "4") (pinfunction "GND_4") (pintype "passive"))
      (node (ref "U6") (pin "5") (pinfunction "GND_5") (pintype "passive"))
      (node (ref "U6") (pin "6") (pinfunction "GND_6") (pintype "passive"))
      (node (ref "U6") (pin "8") (pinfunction "GND_8") (pintype "passive"))
      (node (ref "U6") (pin "9") (pinfunction "GND_9") (pintype "passive"))
      (node (ref "U7") (pin "17") (pinfunction "EP(GND)_17") (pintype "passive"))
      (node (ref "U7") (pin "4") (pinfunction "ACG1_4") (pintype "passive"))
      (node (ref "U7") (pin "5") (pinfunction "ACG2_5") (pintype "passive"))
      (node (ref "U7") (pin "6") (pinfunction "ACG3_6") (pintype "passive"))
      (node (ref "U7") (pin "7") (pinfunction "ACG4_7") (pintype "passive"))
      (node (ref "U7") (pin "8") (pinfunction "ACG5_8") (pintype "passive"))
      (node (ref "U8") (pin "10") (pinfunction "GND_10") (pintype "passive"))
      (node (ref "U8") (pin "11") (pinfunction "GND_11") (pintype "passive"))
      (node (ref "U8") (pin "12") (pinfunction "GND_12") (pintype "passive"))
      (node (ref "U8") (pin "14") (pinfunction "GND_14") (pintype "passive"))
      (node (ref "U8") (pin "17") (pinfunction "GND_17") (pintype "passive"))
      (node (ref "U8") (pin "19") (pinfunction "GND_19") (pintype "passive"))
      (node (ref "U8") (pin "20") (pinfunction "GND_20") (pintype "passive"))
      (node (ref "U8") (pin "21") (pinfunction "GND_21") (pintype "passive"))
      (node (ref "U8") (pin "22") (pinfunction "GND_22") (pintype "passive"))
      (node (ref "U8") (pin "24") (pinfunction "GND_24") (pintype "passive"))
      (node (ref "U8") (pin "25") (pinfunction "GND_25") (pintype "passive"))
      (node (ref "U8") (pin "26") (pinfunction "GND_26") (pintype "passive"))
      (node (ref "U8") (pin "28") (pinfunction "GND_28") (pintype "passive"))
      (node (ref "U8") (pin "29") (pinfunction "GND_29") (pintype "passive"))
      (node (ref "U8") (pin "3") (pinfunction "GND_3") (pintype "passive"))
      (node (ref "U8") (pin "30") (pinfunction "GND_30") (pintype "passive"))
      (node (ref "U8") (pin "31") (pinfunction "GND_31") (pintype "passive"))
      (node (ref "U8") (pin "32") (pinfunction "GND_32") (pintype "passive"))
      (node (ref "U8") (pin "5") (pinfunction "GND_5") (pintype "passive"))
      (node (ref "U8") (pin "8") (pinfunction "GND_8") (pintype "passive"))
      (node (ref "U9") (pin "11") (pinfunction "GND_11") (pintype "power_in"))
      (node (ref "U9") (pin "14") (pinfunction "GND_14") (pintype "power_in"))
      (node (ref "U9") (pin "2") (pinfunction "CM_2") (pintype "input"))
      (node (ref "XMER1") (pin "1") (pinfunction "PRIMARY/GND_1") (pintype "passive"))
      (node (ref "XMER1") (pin "2") (pinfunction "PRIMARY/GND_2") (pintype "passive"))
    )
    (net (code "29") (name "Net-(C20-Pad1)") (class "Default")
      (node (ref "C20") (pin "1") (pinfunction "1_1") (pintype "passive"))
      (node (ref "J1") (pin "1") (pinfunction "1_1") (pintype "passive"))
    )
    (net (code "30") (name "Net-(C28-Pad2)") (class "Default")
      (node (ref "C28") (pin "2") (pinfunction "2_2") (pintype "passive"))
      (node (ref "J3") (pin "1") (pinfunction "1_1") (pintype "passive"))
    )
    (net (code "31") (name "Net-(C30-Pad1)") (class "Default")
      (node (ref "C30") (pin "1") (pinfunction "1_1") (pintype "passive"))
      (node (ref "J2") (pin "1") (pinfunction "1_1") (pintype "passive"))
    )
    (net (code "32") (name "Net-(LED1-A)") (class "Default")
      (node (ref "LED1") (pin "2") (pinfunction "A_2") (pintype "passive"))
      (node (ref "R1") (pin "1") (pinfunction "1_1") (pintype "passive"))
    )
    (net (code "33") (name "Net-(LED2-A)") (class "Default")
      (node (ref "LED2") (pin "2") (pinfunction "A_2") (pintype "passive"))
      (node (ref "R2") (pin "1") (pinfunction "1_1") (pintype "passive"))
    )
    (net (code "34") (name "Net-(U1-VA)") (class "Default")
      (node (ref "C6") (pin "1") (pinfunction "1_1") (pintype "passive"))
      (node (ref "C7") (pin "1") (pinfunction "1_1") (pintype "passive"))
      (node (ref "U1") (pin "3") (pinfunction "VA_3") (pintype "passive"))
    )
    (net (code "35") (name "Net-(U1-VAFB)") (class "Default")
      (node (ref "C7") (pin "2") (pinfunction "2_2") (pintype "passive"))
      (node (ref "U1") (pin "4") (pinfunction "VAFB_4") (pintype "passive"))
    )
    (net (code "36") (name "Net-(U1-VREG)") (class "Default")
      (node (ref "C4") (pin "1") (pinfunction "1_1") (pintype "passive"))
      (node (ref "U1") (pin "7") (pinfunction "VREG_7") (pintype "passive"))
    )
    (net (code "37") (name "Net-(U4-VA)") (class "Default")
      (node (ref "C16") (pin "1") (pinfunction "1_1") (pintype "passive"))
      (node (ref "C17") (pin "1") (pinfunction "1_1") (pintype "passive"))
      (node (ref "U4") (pin "3") (pinfunction "VA_3") (pintype "passive"))
    )
    (net (code "38") (name "Net-(U4-VAFB)") (class "Default")
      (node (ref "C17") (pin "2") (pinfunction "2_2") (pintype "passive"))
      (node (ref "U4") (pin "4") (pinfunction "VAFB_4") (pintype "passive"))
    )
    (net (code "39") (name "Net-(U4-VREG)") (class "Default")
      (node (ref "C14") (pin "1") (pinfunction "1_1") (pintype "passive"))
      (node (ref "U4") (pin "7") (pinfunction "VREG_7") (pintype "passive"))
    )
    (net (code "40") (name "Net-(U6-RF_IN)") (class "Default")
      (node (ref "C20") (pin "2") (pinfunction "2_2") (pintype "passive"))
      (node (ref "U6") (pin "2") (pinfunction "RF_IN_2") (pintype "input"))
    )
    (net (code "41") (name "Net-(U6-RF_OUT&DC_IN)") (class "Default")
      (node (ref "C21") (pin "1") (pinfunction "1_1") (pintype "passive"))
      (node (ref "L1") (pin "1") (pinfunction "1_1") (pintype "passive"))
      (node (ref "U6") (pin "7") (pinfunction "RF_OUT&DC_IN_7") (pintype "output"))
    )
    (net (code "42") (name "Net-(U7-RF1)") (class "Default")
      (node (ref "C21") (pin "2") (pinfunction "2_2") (pintype "passive"))
      (node (ref "U7") (pin "2") (pinfunction "RF1_2") (pintype "passive"))
    )
    (net (code "43") (name "Net-(U7-RF2)") (class "Default")
      (node (ref "C25") (pin "1") (pinfunction "1_1") (pintype "passive"))
      (node (ref "U7") (pin "11") (pinfunction "RF2_11") (pintype "passive"))
    )
    (net (code "44") (name "Net-(U7-V1)") (class "Default")
      (node (ref "R6") (pin "1") (pinfunction "1_1") (pintype "passive"))
      (node (ref "U7") (pin "12") (pinfunction "V1_12") (pintype "passive"))
    )
    (net (code "45") (name "Net-(U7-V2)") (class "Default")
      (node (ref "R7") (pin "1") (pinfunction "1_1") (pintype "passive"))
      (node (ref "U7") (pin "13") (pinfunction "V2_13") (pintype "passive"))
    )
    (net (code "46") (name "Net-(U7-V3)") (class "Default")
      (node (ref "R8") (pin "1") (pinfunction "1_1") (pintype "passive"))
      (node (ref "U7") (pin "14") (pinfunction "V3_14") (pintype "passive"))
    )
    (net (code "47") (name "Net-(U7-V4)") (class "Default")
      (node (ref "R10") (pin "1") (pinfunction "1_1") (pintype "passive"))
      (node (ref "U7") (pin "15") (pinfunction "V4_15") (pintype "passive"))
    )
    (net (code "48") (name "Net-(U7-V5)") (class "Default")
      (node (ref "R11") (pin "1") (pinfunction "1_1") (pintype "passive"))
      (node (ref "U7") (pin "16") (pinfunction "V5_16") (pintype "passive"))
    )
    (net (code "49") (name "Net-(U8-IN_A)") (class "Default")
      (node (ref "U8") (pin "23") (pinfunction "IN_A_23") (pintype "passive"))
      (node (ref "U8") (pin "27") (pinfunction "OUT_A_27") (pintype "output"))
    )
    (net (code "50") (name "Net-(U8-IN_B)") (class "Default")
      (node (ref "U8") (pin "13") (pinfunction "IN_B_13") (pintype "passive"))
      (node (ref "U8") (pin "9") (pinfunction "OUT_B_9") (pintype "output"))
    )
    (net (code "51") (name "Net-(U8-RFIN)") (class "Default")
      (node (ref "C24") (pin "2") (pinfunction "2_2") (pintype "passive"))
      (node (ref "U8") (pin "4") (pinfunction "RFIN_4") (pintype "passive"))
    )
    (net (code "52") (name "Net-(U8-RFOUT)") (class "Default")
      (node (ref "C28") (pin "1") (pinfunction "1_1") (pintype "passive"))
      (node (ref "U8") (pin "18") (pinfunction "RFOUT_18") (pintype "output"))
    )
    (net (code "53") (name "Net-(U8-VBIAS)") (class "Default")
      (node (ref "R9") (pin "2") (pinfunction "2_2") (pintype "passive"))
      (node (ref "U8") (pin "2") (pinfunction "VBIAS_2") (pintype "passive"))
    )
    (net (code "54") (name "Net-(U9-IN+)") (class "Default")
      (node (ref "C27") (pin "2") (pinfunction "2_2") (pintype "passive"))
      (node (ref "U9") (pin "6") (pinfunction "IN+_6") (pintype "input"))
    )
    (net (code "55") (name "Net-(U9-IN-)") (class "Default")
      (node (ref "C25") (pin "2") (pinfunction "2_2") (pintype "passive"))
      (node (ref "U9") (pin "5") (pinfunction "IN-_5") (pintype "input"))
    )
    (net (code "56") (name "Net-(U9-OUT+)") (class "Default")
      (node (ref "R12") (pin "1") (pinfunction "1_1") (pintype "passive"))
      (node (ref "U9") (pin "13") (pinfunction "OUT+_13") (pintype "output"))
    )
    (net (code "57") (name "Net-(U9-OUT-)") (class "Default")
      (node (ref "R13") (pin "1") (pinfunction "1_1") (pintype "passive"))
      (node (ref "U9") (pin "12") (pinfunction "OUT-_12") (pintype "output"))
    )
    (net (code "58") (name "Net-(U10-RF_IN)") (class "Default")
      (node (ref "C30") (pin "2") (pinfunction "2_2") (pintype "passive"))
      (node (ref "U10") (pin "2") (pinfunction "RF_IN_2") (pintype "input"))
    )
    (net (code "59") (name "Net-(U10-RF_OUT&DC_IN)") (class "Default")
      (node (ref "C31") (pin "1") (pinfunction "1_1") (pintype "passive"))
      (node (ref "L2") (pin "1") (pinfunction "1_1") (pintype "passive"))
      (node (ref "U10") (pin "7") (pinfunction "RF_OUT&DC_IN_7") (pintype "output"))
    )
    (net (code "60") (name "Net-(U11-RF1)") (class "Default")
      (node (ref "C31") (pin "2") (pinfunction "2_2") (pintype "passive"))
      (node (ref "U11") (pin "2") (pinfunction "RF1_2") (pintype "passive"))
    )
    (net (code "61") (name "Net-(U11-RF2)") (class "Default")
      (node (ref "C27") (pin "1") (pinfunction "1_1") (pintype "passive"))
      (node (ref "U11") (pin "11") (pinfunction "RF2_11") (pintype "passive"))
    )
    (net (code "62") (name "Net-(U11-V1)") (class "Default")
      (node (ref "R14") (pin "1") (pinfunction "1_1") (pintype "passive"))
      (node (ref "U11") (pin "12") (pinfunction "V1_12") (pintype "passive"))
    )
    (net (code "63") (name "Net-(U11-V2)") (class "Default")
      (node (ref "R15") (pin "1") (pinfunction "1_1") (pintype "passive"))
      (node (ref "U11") (pin "13") (pinfunction "V2_13") (pintype "passive"))
    )
    (net (code "64") (name "Net-(U11-V3)") (class "Default")
      (node (ref "R16") (pin "1") (pinfunction "1_1") (pintype "passive"))
      (node (ref "U11") (pin "14") (pinfunction "V3_14") (pintype "passive"))
    )
    (net (code "65") (name "Net-(U11-V4)") (class "Default")
      (node (ref "R17") (pin "1") (pinfunction "1_1") (pintype "passive"))
      (node (ref "U11") (pin "15") (pinfunction "V4_15") (pintype "passive"))
    )
    (net (code "66") (name "Net-(U11-V5)") (class "Default")
      (node (ref "R18") (pin "1") (pinfunction "1_1") (pintype "passive"))
      (node (ref "U11") (pin "16") (pinfunction "V5_16") (pintype "passive"))
    )
    (net (code "67") (name "Net-(XMER1-PRIMARY_DOT)") (class "Default")
      (node (ref "C24") (pin "1") (pinfunction "1_1") (pintype "passive"))
      (node (ref "XMER1") (pin "3") (pinfunction "PRIMARY_DOT_3") (pintype "passive"))
    )
    (net (code "68") (name "Net-(XMER1-SECONDARY)") (class "Default")
      (node (ref "R13") (pin "2") (pinfunction "2_2") (pintype "passive"))
      (node (ref "XMER1") (pin "4") (pinfunction "SECONDARY_4") (pintype "passive"))
    )
    (net (code "69") (name "Net-(XMER1-SECONDARY_DOT)") (class "Default")
      (node (ref "R12") (pin "2") (pinfunction "2_2") (pintype "passive"))
      (node (ref "XMER1") (pin "6") (pinfunction "SECONDARY_DOT_6") (pintype "passive"))
    )
    (net (code "70") (name "unconnected-(U2-N_C-Pad4)") (class "Default")
      (node (ref "U2") (pin "4") (pinfunction "N_C_4") (pintype "passive"))
    )
    (net (code "71") (name "unconnected-(U3A-PA8-Pad18)") (class "Default")
      (node (ref "U3") (pin "18") (pinfunction "PA8_18") (pintype "bidirectional"))
    )
    (net (code "72") (name "unconnected-(U3A-PA9-Pad19)") (class "Default")
      (node (ref "U3") (pin "19") (pinfunction "PA9_19") (pintype "bidirectional"))
    )
    (net (code "73") (name "unconnected-(U3A-PB4-Pad27)") (class "Default")
      (node (ref "U3") (pin "27") (pinfunction "PB4_27") (pintype "bidirectional"))
    )
    (net (code "74") (name "unconnected-(U3A-PB5-Pad28)") (class "Default")
      (node (ref "U3") (pin "28") (pinfunction "PB5_28") (pintype "bidirectional"))
    )
    (net (code "75") (name "unconnected-(U3A-PC14-OSC32_IN-Pad2)") (class "Default")
      (node (ref "U3") (pin "2") (pinfunction "PC14-OSC32_IN_2") (pintype "bidirectional"))
    )
    (net (code "76") (name "unconnected-(U3A-PC15-OSC32_OUT-Pad3)") (class "Default")
      (node (ref "U3") (pin "3") (pinfunction "PC15-OSC32_OUT_3") (pintype "bidirectional"))
    )
    (net (code "77") (name "unconnected-(U5-N_C-Pad4)") (class "Default")
      (node (ref "U5") (pin "4") (pinfunction "N_C_4") (pintype "passive"))
    )
    (net (code "78") (name "unconnected-(U7-N{slash}C-Pad3)") (class "Default")
      (node (ref "U7") (pin "3") (pinfunction "N/C_3") (pintype "passive"))
    )
    (net (code "79") (name "unconnected-(U7-N{slash}C-Pad9)") (class "Default")
      (node (ref "U7") (pin "9") (pinfunction "N/C_9") (pintype "passive"))
    )
    (net (code "80") (name "unconnected-(U7-N{slash}C-Pad10)") (class "Default")
      (node (ref "U7") (pin "10") (pinfunction "N/C_10") (pintype "passive"))
    )
    (net (code "81") (name "unconnected-(U9-NC-Pad4)") (class "Default")
      (node (ref "U9") (pin "4") (pinfunction "NC_4") (pintype "passive"))
    )
    (net (code "82") (name "unconnected-(U9-NC-Pad7)") (class "Default")
      (node (ref "U9") (pin "7") (pinfunction "NC_7") (pintype "passive"))
    )
    (net (code "83") (name "unconnected-(U11-N{slash}C-Pad3)") (class "Default")
      (node (ref "U11") (pin "3") (pinfunction "N/C_3") (pintype "passive"))
    )
    (net (code "84") (name "unconnected-(U11-N{slash}C-Pad9)") (class "Default")
      (node (ref "U11") (pin "9") (pinfunction "N/C_9") (pintype "passive"))
    )
    (net (code "85") (name "unconnected-(U11-N{slash}C-Pad10)") (class "Default")
      (node (ref "U11") (pin "10") (pinfunction "N/C_10") (pintype "passive"))
    )
    (net (code "86") (name "unconnected-(XMER1-NC-Pad5)") (class "Default")
      (node (ref "XMER1") (pin "5") (pinfunction "NC_5") (pintype "passive"))
    )
  )
)
